# SwitchPower.net
KiCad netlist of a schematic drawn in Altium Designer
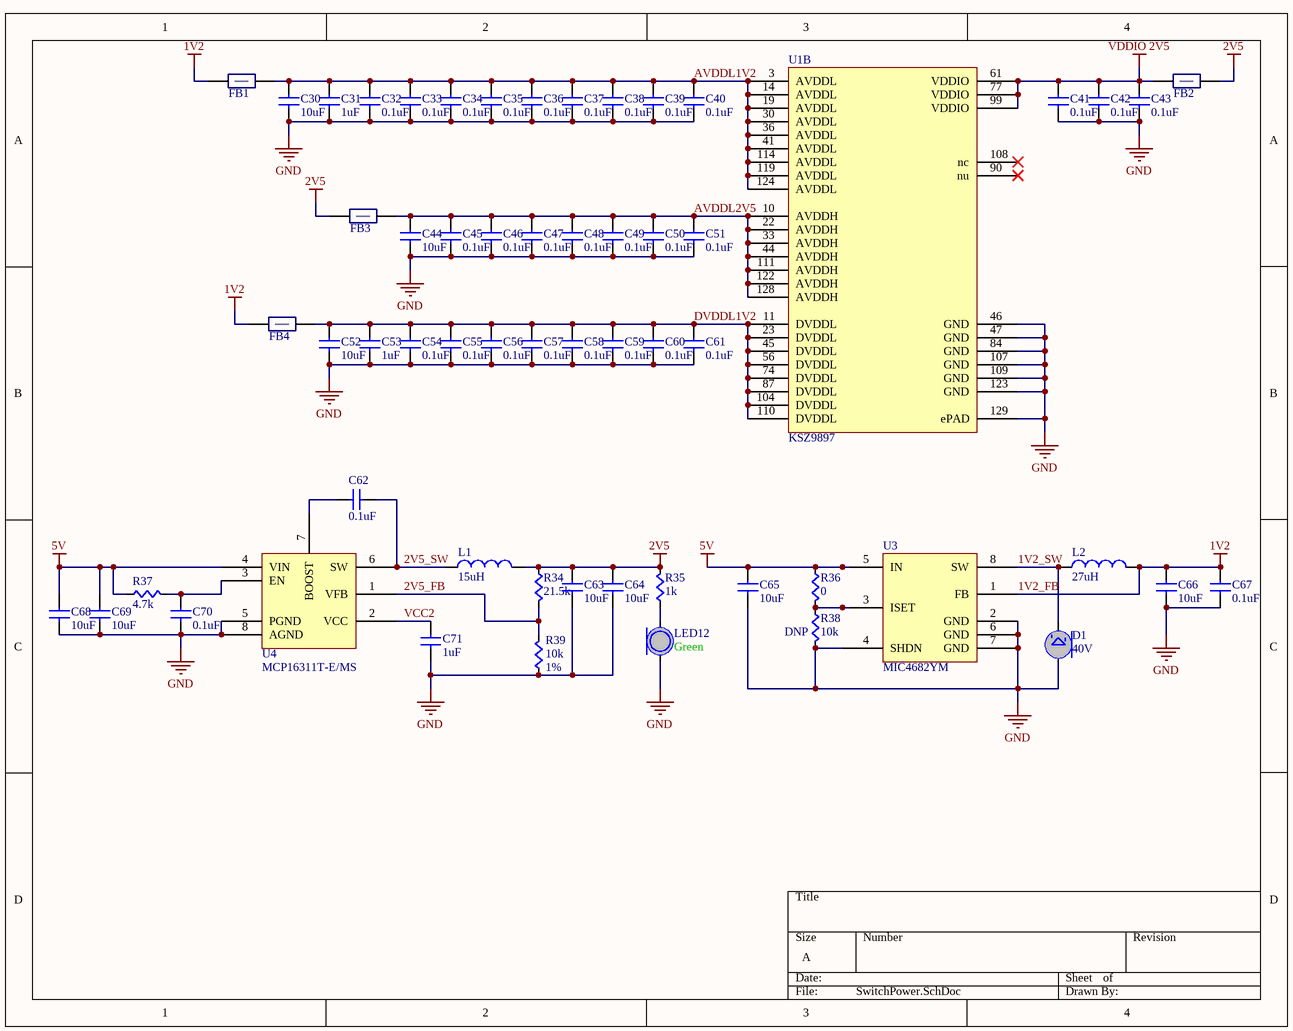
[diagram p0: SwitchPower.SchDoc]

(export (version "E")
  (design (tool "Eeschema 10.0.6"))
  (components
    (comp (ref "C30")
      (value "10uF")
      (footprint "CAPC0603")
      (fields (field (name "Comment") "Cap"))
      (libsource (lib "Passives") (part "Cap"))
    )
    (comp (ref "C31")
      (value "1uF")
      (footprint "CAPC0603")
      (fields (field (name "Comment") "Cap"))
      (libsource (lib "Passives") (part "Cap"))
    )
    (comp (ref "C32")
      (value "0.1uF")
      (footprint "CAPC0603")
      (fields (field (name "Comment") "Cap"))
      (libsource (lib "Passives") (part "Cap"))
    )
    (comp (ref "C33")
      (value "0.1uF")
      (footprint "CAPC0603")
      (fields (field (name "Comment") "Cap"))
      (libsource (lib "Passives") (part "Cap"))
    )
    (comp (ref "C34")
      (value "0.1uF")
      (footprint "CAPC0603")
      (fields (field (name "Comment") "Cap"))
      (libsource (lib "Passives") (part "Cap"))
    )
    (comp (ref "C35")
      (value "0.1uF")
      (footprint "CAPC0603")
      (fields (field (name "Comment") "Cap"))
      (libsource (lib "Passives") (part "Cap"))
    )
    (comp (ref "C36")
      (value "0.1uF")
      (footprint "CAPC0603")
      (fields (field (name "Comment") "Cap"))
      (libsource (lib "Passives") (part "Cap"))
    )
    (comp (ref "C37")
      (value "0.1uF")
      (footprint "CAPC0603")
      (fields (field (name "Comment") "Cap"))
      (libsource (lib "Passives") (part "Cap"))
    )
    (comp (ref "C38")
      (value "0.1uF")
      (footprint "CAPC0603")
      (fields (field (name "Comment") "Cap"))
      (libsource (lib "Passives") (part "Cap"))
    )
    (comp (ref "C39")
      (value "0.1uF")
      (footprint "CAPC0603")
      (fields (field (name "Comment") "Cap"))
      (libsource (lib "Passives") (part "Cap"))
    )
    (comp (ref "C40")
      (value "0.1uF")
      (footprint "CAPC0603")
      (fields (field (name "Comment") "Cap"))
      (libsource (lib "Passives") (part "Cap"))
    )
    (comp (ref "C41")
      (value "0.1uF")
      (footprint "CAPC0603")
      (fields (field (name "Comment") "Cap"))
      (libsource (lib "Passives") (part "Cap"))
    )
    (comp (ref "C42")
      (value "0.1uF")
      (footprint "CAPC0603")
      (fields (field (name "Comment") "Cap"))
      (libsource (lib "Passives") (part "Cap"))
    )
    (comp (ref "C43")
      (value "0.1uF")
      (footprint "CAPC0603")
      (fields (field (name "Comment") "Cap"))
      (libsource (lib "Passives") (part "Cap"))
    )
    (comp (ref "C44")
      (value "10uF")
      (footprint "CAPC0603")
      (fields (field (name "Comment") "Cap"))
      (libsource (lib "Passives") (part "Cap"))
    )
    (comp (ref "C45")
      (value "0.1uF")
      (footprint "CAPC0603")
      (fields (field (name "Comment") "Cap"))
      (libsource (lib "Passives") (part "Cap"))
    )
    (comp (ref "C46")
      (value "0.1uF")
      (footprint "CAPC0603")
      (fields (field (name "Comment") "Cap"))
      (libsource (lib "Passives") (part "Cap"))
    )
    (comp (ref "C47")
      (value "0.1uF")
      (footprint "CAPC0603")
      (fields (field (name "Comment") "Cap"))
      (libsource (lib "Passives") (part "Cap"))
    )
    (comp (ref "C48")
      (value "0.1uF")
      (footprint "CAPC0603")
      (fields (field (name "Comment") "Cap"))
      (libsource (lib "Passives") (part "Cap"))
    )
    (comp (ref "C49")
      (value "0.1uF")
      (footprint "CAPC0603")
      (fields (field (name "Comment") "Cap"))
      (libsource (lib "Passives") (part "Cap"))
    )
    (comp (ref "C50")
      (value "0.1uF")
      (footprint "CAPC0603")
      (fields (field (name "Comment") "Cap"))
      (libsource (lib "Passives") (part "Cap"))
    )
    (comp (ref "C51")
      (value "0.1uF")
      (footprint "CAPC0603")
      (fields (field (name "Comment") "Cap"))
      (libsource (lib "Passives") (part "Cap"))
    )
    (comp (ref "C52")
      (value "10uF")
      (footprint "CAPC0603")
      (fields (field (name "Comment") "Cap"))
      (libsource (lib "Passives") (part "Cap"))
    )
    (comp (ref "C53")
      (value "1uF")
      (footprint "CAPC0603")
      (fields (field (name "Comment") "Cap"))
      (libsource (lib "Passives") (part "Cap"))
    )
    (comp (ref "C54")
      (value "0.1uF")
      (footprint "CAPC0603")
      (fields (field (name "Comment") "Cap"))
      (libsource (lib "Passives") (part "Cap"))
    )
    (comp (ref "C55")
      (value "0.1uF")
      (footprint "CAPC0603")
      (fields (field (name "Comment") "Cap"))
      (libsource (lib "Passives") (part "Cap"))
    )
    (comp (ref "C56")
      (value "0.1uF")
      (footprint "CAPC0603")
      (fields (field (name "Comment") "Cap"))
      (libsource (lib "Passives") (part "Cap"))
    )
    (comp (ref "C57")
      (value "0.1uF")
      (footprint "CAPC0603")
      (fields (field (name "Comment") "Cap"))
      (libsource (lib "Passives") (part "Cap"))
    )
    (comp (ref "C58")
      (value "0.1uF")
      (footprint "CAPC0603")
      (fields (field (name "Comment") "Cap"))
      (libsource (lib "Passives") (part "Cap"))
    )
    (comp (ref "C59")
      (value "0.1uF")
      (footprint "CAPC0603")
      (fields (field (name "Comment") "Cap"))
      (libsource (lib "Passives") (part "Cap"))
    )
    (comp (ref "C60")
      (value "0.1uF")
      (footprint "CAPC0603")
      (fields (field (name "Comment") "Cap"))
      (libsource (lib "Passives") (part "Cap"))
    )
    (comp (ref "C61")
      (value "0.1uF")
      (footprint "CAPC0603")
      (fields (field (name "Comment") "Cap"))
      (libsource (lib "Passives") (part "Cap"))
    )
    (comp (ref "C62")
      (value "0.1uF")
      (footprint "CAPC0603")
      (fields (field (name "Comment") "Cap"))
      (libsource (lib "Passives") (part "Cap"))
    )
    (comp (ref "C63")
      (value "10uF")
      (footprint "CAPC0603")
      (fields (field (name "Comment") "Cap"))
      (libsource (lib "Passives") (part "Cap"))
    )
    (comp (ref "C64")
      (value "10uF")
      (footprint "CAPC0603")
      (fields (field (name "Comment") "Cap"))
      (libsource (lib "Passives") (part "Cap"))
    )
    (comp (ref "C65")
      (value "10uF")
      (footprint "CAPC0603")
      (fields (field (name "Comment") "Cap"))
      (libsource (lib "Passives") (part "Cap"))
    )
    (comp (ref "C66")
      (value "10uF")
      (footprint "CAPC0603")
      (fields (field (name "Comment") "Cap"))
      (libsource (lib "Passives") (part "Cap"))
    )
    (comp (ref "C67")
      (value "0.1uF")
      (footprint "CAPC0603")
      (fields (field (name "Comment") "Cap"))
      (libsource (lib "Passives") (part "Cap"))
    )
    (comp (ref "C68")
      (value "10uF")
      (footprint "CAPC0603")
      (fields (field (name "Comment") "Cap"))
      (libsource (lib "Passives") (part "Cap"))
    )
    (comp (ref "C69")
      (value "10uF")
      (footprint "CAPC0603")
      (fields (field (name "Comment") "Cap"))
      (libsource (lib "Passives") (part "Cap"))
    )
    (comp (ref "C70")
      (value "0.1uF")
      (footprint "CAPC0603")
      (fields (field (name "Comment") "Cap"))
      (libsource (lib "Passives") (part "Cap"))
    )
    (comp (ref "C71")
      (value "1uF")
      (footprint "CAPC0603")
      (fields (field (name "Comment") "Cap"))
      (libsource (lib "Passives") (part "Cap"))
    )
    (comp (ref "D1")
      (value "Zener")
      (footprint "SMASeries")
      (description "Zener Diode")
      (fields (field (name "ZENER VOLTAGE") "40V"))
      (libsource (lib "Semiconductors") (part "Zener"))
    )
    (comp (ref "FB1")
      (value "FBead")
      (footprint "RES0603")
      (description "Ferrite Bead")
      (libsource (lib "Passives") (part "FBead"))
    )
    (comp (ref "FB2")
      (value "FBead")
      (footprint "RES0603")
      (description "Ferrite Bead")
      (libsource (lib "Passives") (part "FBead"))
    )
    (comp (ref "FB3")
      (value "FBead")
      (footprint "RES0603")
      (description "Ferrite Bead")
      (libsource (lib "Passives") (part "FBead"))
    )
    (comp (ref "FB4")
      (value "FBead")
      (footprint "RES0603")
      (description "Ferrite Bead")
      (libsource (lib "Passives") (part "FBead"))
    )
    (comp (ref "L1")
      (value "Inductor")
      (footprint "Passives:RES0603")
      (fields (field (name "INDUCTANCE") "15uH"))
      (libsource (lib "Passives") (part "Inductor"))
    )
    (comp (ref "L2")
      (value "Inductor")
      (footprint "Passives:RES0603")
      (fields (field (name "INDUCTANCE") "27uH"))
      (libsource (lib "Passives") (part "Inductor"))
    )
    (comp (ref "LED12")
      (value "LED")
      (footprint "LED0603")
      (fields (field (name "COLOR") "Green"))
      (libsource (lib "Semiconductors") (part "LED"))
    )
    (comp (ref "R34")
      (value "21.5k")
      (footprint "RES0603")
      (fields (field (name "Comment") "Res"))
      (libsource (lib "Passives") (part "Res"))
    )
    (comp (ref "R35")
      (value "1k")
      (footprint "RES0603")
      (fields (field (name "Comment") "Res"))
      (libsource (lib "Passives") (part "Res"))
    )
    (comp (ref "R36")
      (value "0")
      (footprint "RES0603")
      (fields (field (name "Comment") "Res"))
      (libsource (lib "Passives") (part "Res"))
    )
    (comp (ref "R37")
      (value "4.7k")
      (footprint "RES0603")
      (fields (field (name "Comment") "Res"))
      (libsource (lib "Passives") (part "Res"))
    )
    (comp (ref "R38")
      (value "10k")
      (footprint "RES0603")
      (fields (field (name "DNP") "DNP") (field (name "Comment") "Res"))
      (libsource (lib "Passives") (part "Res"))
    )
    (comp (ref "R39")
      (value "10k")
      (footprint "RES0603")
      (fields (field (name "TOLERANCE") "1%") (field (name "Comment") "Res"))
      (libsource (lib "Passives") (part "Res"))
    )
    (comp (ref "U1")
      (value "KSZ9897")
      (footprint "ICs:128-TQFP")
      (description "Ethernet Switch 10/100/1000 Base-T PHY I²C, SPI Interface 128-TQFP (14x14)")
      (libsource (lib "ICs") (part "KSZ9897RTXC-TR"))
    )
    (comp (ref "U3")
      (value "MIC4682YM")
      (footprint "ICs:8-SOIC")
      (description "IC REG BUCK ADJ 2A 8SOIC")
      (libsource (lib "ICs") (part "MIC4682YM"))
    )
    (comp (ref "U4")
      (value "MCP16311T-E/MS")
      (footprint "ICs:TSSOP-8")
      (description "IC REG BUCK ADJ 1A SYNC 8MSOP")
      (libsource (lib "ICs") (part "MCP16311T-E/MS"))
    )
  )
  (nets
    (net (code "1") (name "/1V2_SW") (class "Default")
      (node (ref "D1") (pin "C") (pinfunction "C_C") (pintype "passive"))
      (node (ref "L2") (pin "1") (pinfunction "A_1") (pintype "passive"))
      (node (ref "U3") (pin "8") (pinfunction "SW_8") (pintype "passive"))
    )
    (net (code "2") (name "/2V5_FB") (class "Default")
      (node (ref "R34") (pin "1") (pinfunction "A_1") (pintype "passive"))
      (node (ref "R39") (pin "1") (pinfunction "A_1") (pintype "passive"))
      (node (ref "U4") (pin "1") (pinfunction "VFB_1") (pintype "passive"))
    )
    (net (code "3") (name "/2V5_SW") (class "Default")
      (node (ref "C62") (pin "2") (pinfunction "B_2") (pintype "passive"))
      (node (ref "L1") (pin "1") (pinfunction "A_1") (pintype "passive"))
      (node (ref "U4") (pin "6") (pinfunction "SW_6") (pintype "passive"))
    )
    (net (code "4") (name "/AVDDL1V2") (class "Default")
      (node (ref "C30") (pin "1") (pinfunction "A_1") (pintype "passive"))
      (node (ref "C31") (pin "1") (pinfunction "A_1") (pintype "passive"))
      (node (ref "C32") (pin "1") (pinfunction "A_1") (pintype "passive"))
      (node (ref "C33") (pin "1") (pinfunction "A_1") (pintype "passive"))
      (node (ref "C34") (pin "1") (pinfunction "A_1") (pintype "passive"))
      (node (ref "C35") (pin "1") (pinfunction "A_1") (pintype "passive"))
      (node (ref "C36") (pin "1") (pinfunction "A_1") (pintype "passive"))
      (node (ref "C37") (pin "1") (pinfunction "A_1") (pintype "passive"))
      (node (ref "C38") (pin "1") (pinfunction "A_1") (pintype "passive"))
      (node (ref "C39") (pin "1") (pinfunction "A_1") (pintype "passive"))
      (node (ref "C40") (pin "1") (pinfunction "A_1") (pintype "passive"))
      (node (ref "FB1") (pin "2") (pinfunction "B_2") (pintype "passive"))
      (node (ref "U1") (pin "114") (pinfunction "AVDDL_114") (pintype "passive"))
      (node (ref "U1") (pin "119") (pinfunction "AVDDL_119") (pintype "passive"))
      (node (ref "U1") (pin "124") (pinfunction "AVDDL_124") (pintype "passive"))
      (node (ref "U1") (pin "14") (pinfunction "AVDDL_14") (pintype "passive"))
      (node (ref "U1") (pin "19") (pinfunction "AVDDL_19") (pintype "passive"))
      (node (ref "U1") (pin "3") (pinfunction "AVDDL_3") (pintype "passive"))
      (node (ref "U1") (pin "30") (pinfunction "AVDDL_30") (pintype "passive"))
      (node (ref "U1") (pin "36") (pinfunction "AVDDL_36") (pintype "passive"))
      (node (ref "U1") (pin "41") (pinfunction "AVDDL_41") (pintype "passive"))
    )
    (net (code "5") (name "/AVDDL2V5") (class "Default")
      (node (ref "C44") (pin "1") (pinfunction "A_1") (pintype "passive"))
      (node (ref "C45") (pin "1") (pinfunction "A_1") (pintype "passive"))
      (node (ref "C46") (pin "1") (pinfunction "A_1") (pintype "passive"))
      (node (ref "C47") (pin "1") (pinfunction "A_1") (pintype "passive"))
      (node (ref "C48") (pin "1") (pinfunction "A_1") (pintype "passive"))
      (node (ref "C49") (pin "1") (pinfunction "A_1") (pintype "passive"))
      (node (ref "C50") (pin "1") (pinfunction "A_1") (pintype "passive"))
      (node (ref "C51") (pin "1") (pinfunction "A_1") (pintype "passive"))
      (node (ref "FB3") (pin "2") (pinfunction "B_2") (pintype "passive"))
      (node (ref "U1") (pin "10") (pinfunction "AVDDH_10") (pintype "passive"))
      (node (ref "U1") (pin "111") (pinfunction "AVDDH_111") (pintype "passive"))
      (node (ref "U1") (pin "122") (pinfunction "AVDDH_122") (pintype "passive"))
      (node (ref "U1") (pin "128") (pinfunction "AVDDH_128") (pintype "passive"))
      (node (ref "U1") (pin "22") (pinfunction "AVDDH_22") (pintype "passive"))
      (node (ref "U1") (pin "33") (pinfunction "AVDDH_33") (pintype "passive"))
      (node (ref "U1") (pin "44") (pinfunction "AVDDH_44") (pintype "passive"))
    )
    (net (code "6") (name "/DVDDL1V2") (class "Default")
      (node (ref "C52") (pin "1") (pinfunction "A_1") (pintype "passive"))
      (node (ref "C53") (pin "1") (pinfunction "A_1") (pintype "passive"))
      (node (ref "C54") (pin "1") (pinfunction "A_1") (pintype "passive"))
      (node (ref "C55") (pin "1") (pinfunction "A_1") (pintype "passive"))
      (node (ref "C56") (pin "1") (pinfunction "A_1") (pintype "passive"))
      (node (ref "C57") (pin "1") (pinfunction "A_1") (pintype "passive"))
      (node (ref "C58") (pin "1") (pinfunction "A_1") (pintype "passive"))
      (node (ref "C59") (pin "1") (pinfunction "A_1") (pintype "passive"))
      (node (ref "C60") (pin "1") (pinfunction "A_1") (pintype "passive"))
      (node (ref "C61") (pin "1") (pinfunction "A_1") (pintype "passive"))
      (node (ref "FB4") (pin "2") (pinfunction "B_2") (pintype "passive"))
      (node (ref "U1") (pin "104") (pinfunction "DVDDL_104") (pintype "passive"))
      (node (ref "U1") (pin "11") (pinfunction "DVDDL_11") (pintype "passive"))
      (node (ref "U1") (pin "110") (pinfunction "DVDDL_110") (pintype "passive"))
      (node (ref "U1") (pin "23") (pinfunction "DVDDL_23") (pintype "passive"))
      (node (ref "U1") (pin "45") (pinfunction "DVDDL_45") (pintype "passive"))
      (node (ref "U1") (pin "56") (pinfunction "DVDDL_56") (pintype "passive"))
      (node (ref "U1") (pin "74") (pinfunction "DVDDL_74") (pintype "passive"))
      (node (ref "U1") (pin "87") (pinfunction "DVDDL_87") (pintype "passive"))
    )
    (net (code "7") (name "/VCC2") (class "Default")
      (node (ref "C71") (pin "1") (pinfunction "A_1") (pintype "passive"))
      (node (ref "U4") (pin "2") (pinfunction "VCC_2") (pintype "passive"))
    )
    (net (code "8") (name "1V2") (class "Default")
      (node (ref "C66") (pin "1") (pinfunction "A_1") (pintype "passive"))
      (node (ref "C67") (pin "1") (pinfunction "A_1") (pintype "passive"))
      (node (ref "FB1") (pin "1") (pinfunction "A_1") (pintype "passive"))
      (node (ref "FB4") (pin "1") (pinfunction "A_1") (pintype "passive"))
      (node (ref "L2") (pin "2") (pinfunction "B_2") (pintype "passive"))
      (node (ref "U3") (pin "1") (pinfunction "FB_1") (pintype "passive"))
    )
    (net (code "9") (name "2V5") (class "Default")
      (node (ref "C63") (pin "1") (pinfunction "A_1") (pintype "passive"))
      (node (ref "C64") (pin "1") (pinfunction "A_1") (pintype "passive"))
      (node (ref "FB2") (pin "2") (pinfunction "B_2") (pintype "passive"))
      (node (ref "FB3") (pin "1") (pinfunction "A_1") (pintype "passive"))
      (node (ref "L1") (pin "2") (pinfunction "B_2") (pintype "passive"))
      (node (ref "R34") (pin "2") (pinfunction "B_2") (pintype "passive"))
      (node (ref "R35") (pin "1") (pinfunction "A_1") (pintype "passive"))
    )
    (net (code "10") (name "5V") (class "Default")
      (node (ref "C65") (pin "1") (pinfunction "A_1") (pintype "passive"))
      (node (ref "C68") (pin "1") (pinfunction "A_1") (pintype "passive"))
      (node (ref "C69") (pin "1") (pinfunction "A_1") (pintype "passive"))
      (node (ref "R36") (pin "2") (pinfunction "B_2") (pintype "passive"))
      (node (ref "R37") (pin "2") (pinfunction "B_2") (pintype "passive"))
      (node (ref "U3") (pin "5") (pinfunction "IN_5") (pintype "passive"))
      (node (ref "U4") (pin "4") (pinfunction "VIN_4") (pintype "passive"))
    )
    (net (code "11") (name "GND") (class "Default")
      (node (ref "C30") (pin "2") (pinfunction "B_2") (pintype "passive"))
      (node (ref "C31") (pin "2") (pinfunction "B_2") (pintype "passive"))
      (node (ref "C32") (pin "2") (pinfunction "B_2") (pintype "passive"))
      (node (ref "C33") (pin "2") (pinfunction "B_2") (pintype "passive"))
      (node (ref "C34") (pin "2") (pinfunction "B_2") (pintype "passive"))
      (node (ref "C35") (pin "2") (pinfunction "B_2") (pintype "passive"))
      (node (ref "C36") (pin "2") (pinfunction "B_2") (pintype "passive"))
      (node (ref "C37") (pin "2") (pinfunction "B_2") (pintype "passive"))
      (node (ref "C38") (pin "2") (pinfunction "B_2") (pintype "passive"))
      (node (ref "C39") (pin "2") (pinfunction "B_2") (pintype "passive"))
      (node (ref "C40") (pin "2") (pinfunction "B_2") (pintype "passive"))
      (node (ref "C41") (pin "2") (pinfunction "B_2") (pintype "passive"))
      (node (ref "C42") (pin "2") (pinfunction "B_2") (pintype "passive"))
      (node (ref "C43") (pin "2") (pinfunction "B_2") (pintype "passive"))
      (node (ref "C44") (pin "2") (pinfunction "B_2") (pintype "passive"))
      (node (ref "C45") (pin "2") (pinfunction "B_2") (pintype "passive"))
      (node (ref "C46") (pin "2") (pinfunction "B_2") (pintype "passive"))
      (node (ref "C47") (pin "2") (pinfunction "B_2") (pintype "passive"))
      (node (ref "C48") (pin "2") (pinfunction "B_2") (pintype "passive"))
      (node (ref "C49") (pin "2") (pinfunction "B_2") (pintype "passive"))
      (node (ref "C50") (pin "2") (pinfunction "B_2") (pintype "passive"))
      (node (ref "C51") (pin "2") (pinfunction "B_2") (pintype "passive"))
      (node (ref "C52") (pin "2") (pinfunction "B_2") (pintype "passive"))
      (node (ref "C53") (pin "2") (pinfunction "B_2") (pintype "passive"))
      (node (ref "C54") (pin "2") (pinfunction "B_2") (pintype "passive"))
      (node (ref "C55") (pin "2") (pinfunction "B_2") (pintype "passive"))
      (node (ref "C56") (pin "2") (pinfunction "B_2") (pintype "passive"))
      (node (ref "C57") (pin "2") (pinfunction "B_2") (pintype "passive"))
      (node (ref "C58") (pin "2") (pinfunction "B_2") (pintype "passive"))
      (node (ref "C59") (pin "2") (pinfunction "B_2") (pintype "passive"))
      (node (ref "C60") (pin "2") (pinfunction "B_2") (pintype "passive"))
      (node (ref "C61") (pin "2") (pinfunction "B_2") (pintype "passive"))
      (node (ref "C63") (pin "2") (pinfunction "B_2") (pintype "passive"))
      (node (ref "C64") (pin "2") (pinfunction "B_2") (pintype "passive"))
      (node (ref "C65") (pin "2") (pinfunction "B_2") (pintype "passive"))
      (node (ref "C66") (pin "2") (pinfunction "B_2") (pintype "passive"))
      (node (ref "C67") (pin "2") (pinfunction "B_2") (pintype "passive"))
      (node (ref "C68") (pin "2") (pinfunction "B_2") (pintype "passive"))
      (node (ref "C69") (pin "2") (pinfunction "B_2") (pintype "passive"))
      (node (ref "C70") (pin "2") (pinfunction "B_2") (pintype "passive"))
      (node (ref "C71") (pin "2") (pinfunction "B_2") (pintype "passive"))
      (node (ref "D1") (pin "A") (pinfunction "A_A") (pintype "passive"))
      (node (ref "LED12") (pin "C") (pinfunction "C_C") (pintype "passive"))
      (node (ref "R38") (pin "1") (pinfunction "A_1") (pintype "passive"))
      (node (ref "R39") (pin "2") (pinfunction "B_2") (pintype "passive"))
      (node (ref "U1") (pin "107") (pinfunction "GND_107") (pintype "passive"))
      (node (ref "U1") (pin "109") (pinfunction "GND_109") (pintype "passive"))
      (node (ref "U1") (pin "123") (pinfunction "GND_123") (pintype "passive"))
      (node (ref "U1") (pin "129") (pinfunction "ePAD_129") (pintype "passive"))
      (node (ref "U1") (pin "46") (pinfunction "GND_46") (pintype "passive"))
      (node (ref "U1") (pin "47") (pinfunction "GND_47") (pintype "passive"))
      (node (ref "U1") (pin "84") (pinfunction "GND_84") (pintype "passive"))
      (node (ref "U3") (pin "2") (pinfunction "GND_2") (pintype "passive"))
      (node (ref "U3") (pin "4") (pinfunction "SHDN_4") (pintype "passive"))
      (node (ref "U3") (pin "6") (pinfunction "GND_6") (pintype "passive"))
      (node (ref "U3") (pin "7") (pinfunction "GND_7") (pintype "passive"))
      (node (ref "U4") (pin "5") (pinfunction "PGND_5") (pintype "passive"))
      (node (ref "U4") (pin "8") (pinfunction "AGND_8") (pintype "passive"))
    )
    (net (code "12") (name "Net-(C62-A)") (class "Default")
      (node (ref "C62") (pin "1") (pinfunction "A_1") (pintype "passive"))
      (node (ref "U4") (pin "7") (pinfunction "BOOST_7") (pintype "passive"))
    )
    (net (code "13") (name "Net-(C70-A)") (class "Default")
      (node (ref "C70") (pin "1") (pinfunction "A_1") (pintype "passive"))
      (node (ref "R37") (pin "1") (pinfunction "A_1") (pintype "passive"))
      (node (ref "U4") (pin "3") (pinfunction "EN_3") (pintype "passive"))
    )
    (net (code "14") (name "Net-(R35-B)") (class "Default")
      (node (ref "LED12") (pin "A") (pinfunction "A_A") (pintype "passive"))
      (node (ref "R35") (pin "2") (pinfunction "B_2") (pintype "passive"))
    )
    (net (code "15") (name "Net-(R36-A)") (class "Default")
      (node (ref "R36") (pin "1") (pinfunction "A_1") (pintype "passive"))
      (node (ref "R38") (pin "2") (pinfunction "B_2") (pintype "passive"))
      (node (ref "U3") (pin "3") (pinfunction "ISET_3") (pintype "passive"))
    )
    (net (code "16") (name "VDDIO 2V5") (class "Default")
      (node (ref "C41") (pin "1") (pinfunction "A_1") (pintype "passive"))
      (node (ref "C42") (pin "1") (pinfunction "A_1") (pintype "passive"))
      (node (ref "C43") (pin "1") (pinfunction "A_1") (pintype "passive"))
      (node (ref "FB2") (pin "1") (pinfunction "A_1") (pintype "passive"))
      (node (ref "U1") (pin "61") (pinfunction "VDDIO_61") (pintype "passive"))
      (node (ref "U1") (pin "77") (pinfunction "VDDIO_77") (pintype "passive"))
      (node (ref "U1") (pin "99") (pinfunction "VDDIO_99") (pintype "passive"))
    )
    (net (code "17") (name "unconnected-(U1B-nc-Pad108)") (class "Default")
      (node (ref "U1") (pin "108") (pinfunction "nc_108") (pintype "passive+no_connect"))
    )
    (net (code "18") (name "unconnected-(U1B-nu-Pad90)") (class "Default")
      (node (ref "U1") (pin "90") (pinfunction "nu_90") (pintype "passive+no_connect"))
    )
  )
)
